# audio_breakout.net
KiCad netlist of a schematic drawn in EAGLE
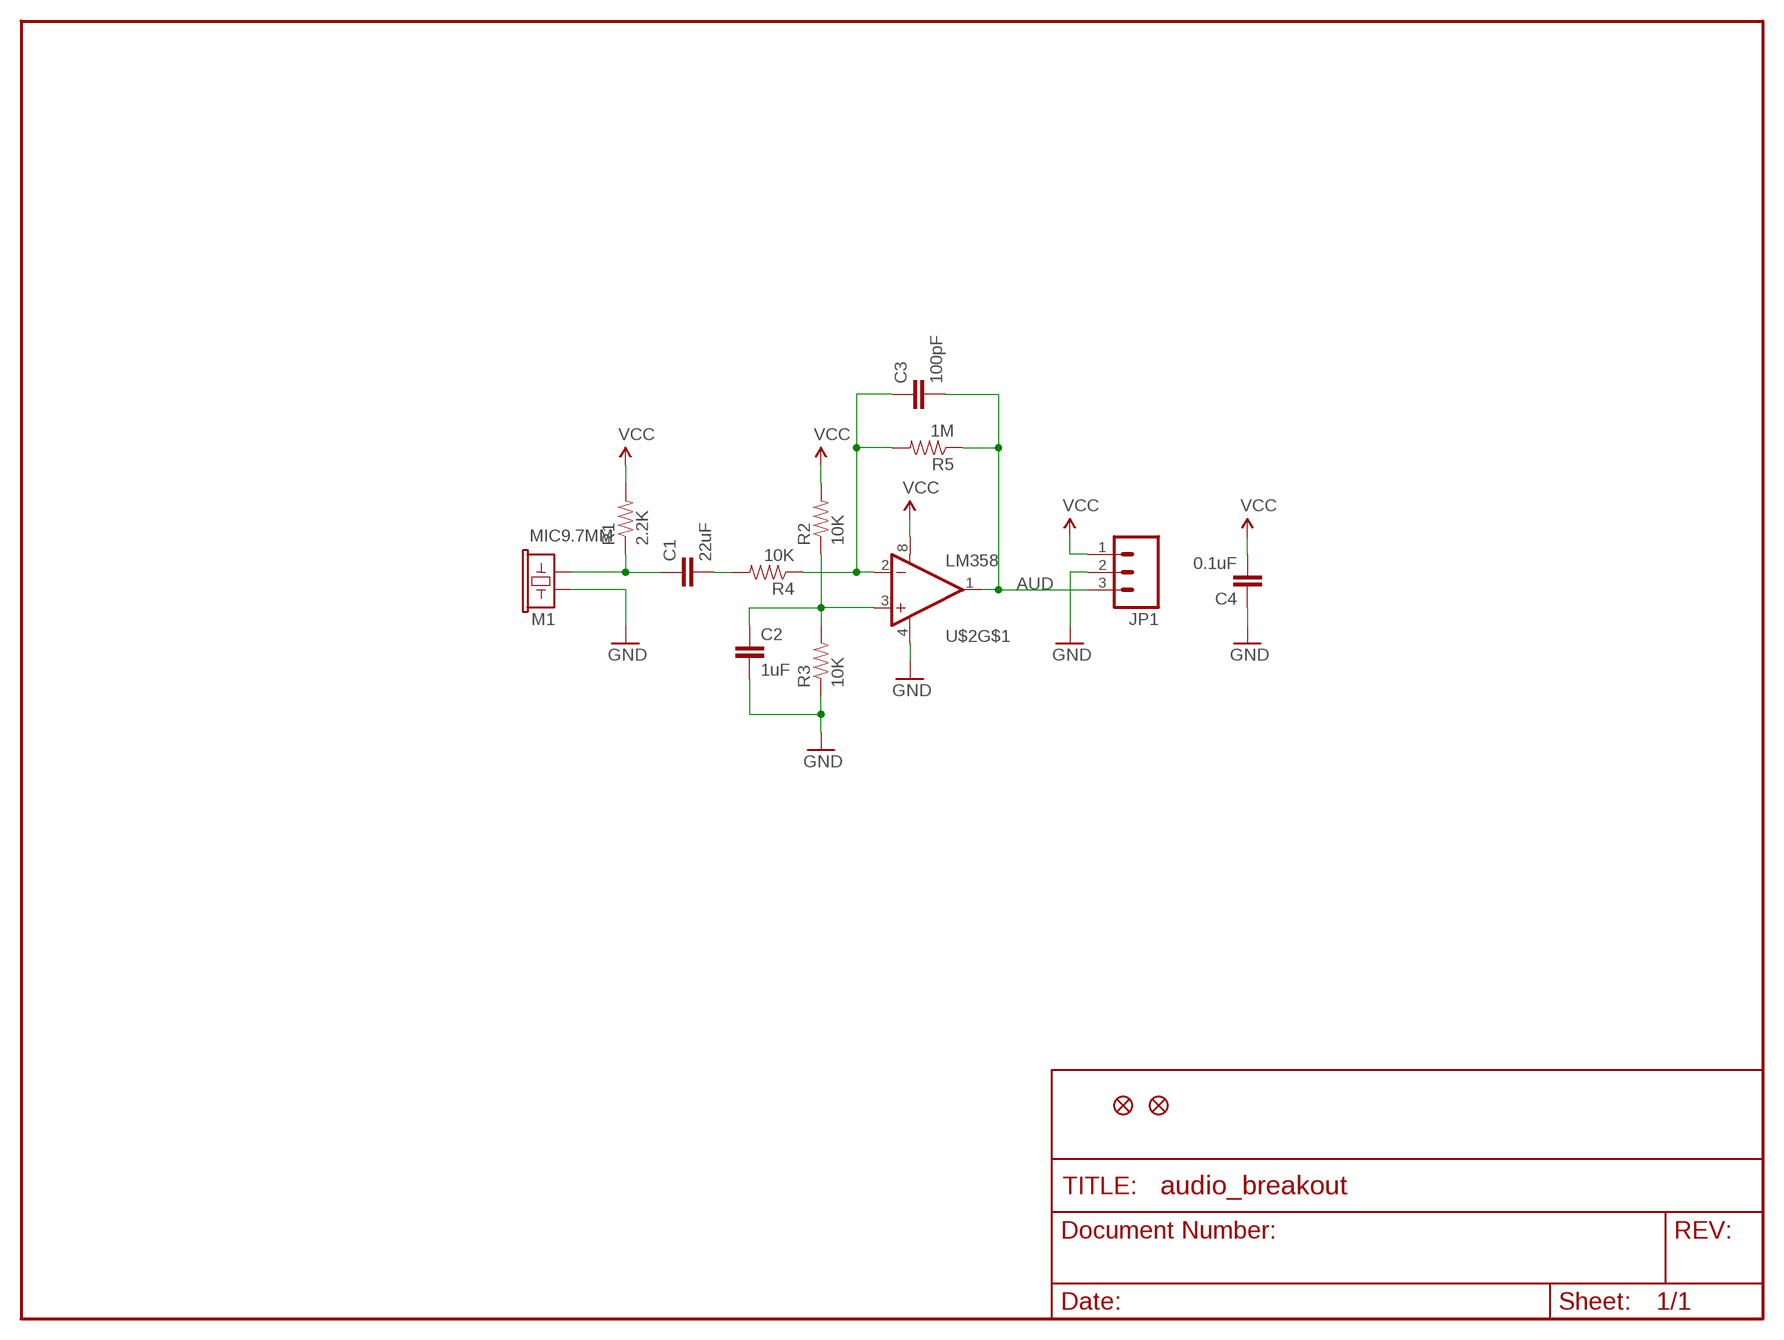
[diagram p0: schematic, sheet 1]

(export (version "E")
  (design (tool "Eeschema 10.0.6"))
  (components
    (comp (ref "C1")
      (value "22uF")
      (footprint "eagle-import:1206")
      (libsource (lib "eagle-import") (part "CAP1206"))
    )
    (comp (ref "C2")
      (value "1uF")
      (footprint "eagle-import:1206")
      (libsource (lib "eagle-import") (part "CAP1206"))
    )
    (comp (ref "C3")
      (value "100pF")
      (footprint "eagle-import:1206")
      (libsource (lib "eagle-import") (part "CAP1206"))
    )
    (comp (ref "C4")
      (value "0.1uF")
      (footprint "eagle-import:1206")
      (libsource (lib "eagle-import") (part "CAP1206"))
    )
    (comp (ref "JP1")
      (value "M03PTH")
      (footprint "eagle-import:1X03")
      (libsource (lib "eagle-import") (part "M03PTH"))
    )
    (comp (ref "JP2")
      (value "FIDUCIAL1X2")
      (footprint "eagle-import:FIDUCIAL-1X2")
      (libsource (lib "eagle-import") (part "FIDUCIAL1X2"))
    )
    (comp (ref "JP3")
      (value "FIDUCIAL1X2")
      (footprint "eagle-import:FIDUCIAL-1X2")
      (libsource (lib "eagle-import") (part "FIDUCIAL1X2"))
    )
    (comp (ref "M1")
      (value "MIC9.7MM")
      (footprint "eagle-import:MIC-9.7MM")
      (libsource (lib "eagle-import") (part "MIC9.7MM"))
    )
    (comp (ref "R1")
      (value "2.2K")
      (footprint "eagle-import:1206")
      (libsource (lib "eagle-import") (part "RESISTOR1206"))
    )
    (comp (ref "R2")
      (value "10K")
      (footprint "eagle-import:1206")
      (libsource (lib "eagle-import") (part "RESISTOR1206"))
    )
    (comp (ref "R3")
      (value "10K")
      (footprint "eagle-import:1206")
      (libsource (lib "eagle-import") (part "RESISTOR1206"))
    )
    (comp (ref "R4")
      (value "10K")
      (footprint "eagle-import:1206")
      (libsource (lib "eagle-import") (part "RESISTOR1206"))
    )
    (comp (ref "R5")
      (value "1M")
      (footprint "eagle-import:1206")
      (libsource (lib "eagle-import") (part "RESISTOR1206"))
    )
    (comp (ref "U$2")
      (value "LM358")
      (footprint "eagle-import:DIP08")
      (libsource (lib "eagle-import") (part "LM358"))
    )
  )
  (nets
    (net (code "1") (name "/AUD") (class "Default")
      (node (ref "C3") (pin "2") (pinfunction "2_2") (pintype "passive"))
      (node (ref "JP1") (pin "3") (pinfunction "3_3") (pintype "passive"))
      (node (ref "R5") (pin "1") (pinfunction "1_1") (pintype "passive"))
      (node (ref "U$2") (pin "1") (pinfunction "OUT_1") (pintype "output"))
    )
    (net (code "2") (name "GND") (class "Default")
      (node (ref "C2") (pin "2") (pinfunction "2_2") (pintype "passive"))
      (node (ref "C4") (pin "1") (pinfunction "1_1") (pintype "passive"))
      (node (ref "JP1") (pin "2") (pinfunction "2_2") (pintype "passive"))
      (node (ref "M1") (pin "2") (pinfunction "2_2") (pintype "passive"))
      (node (ref "R3") (pin "1") (pinfunction "1_1") (pintype "passive"))
      (node (ref "U$2") (pin "4") (pinfunction "V-_4") (pintype "power_in"))
    )
    (net (code "3") (name "Net-(C1-Pad1)") (class "Default")
      (node (ref "C1") (pin "1") (pinfunction "1_1") (pintype "passive"))
      (node (ref "M1") (pin "1") (pinfunction "1_1") (pintype "passive"))
      (node (ref "R1") (pin "1") (pinfunction "1_1") (pintype "passive"))
    )
    (net (code "4") (name "Net-(C1-Pad2)") (class "Default")
      (node (ref "C1") (pin "2") (pinfunction "2_2") (pintype "passive"))
      (node (ref "R4") (pin "2") (pinfunction "2_2") (pintype "passive"))
    )
    (net (code "5") (name "Net-(U$2A-+IN)") (class "Default")
      (node (ref "C2") (pin "1") (pinfunction "1_1") (pintype "passive"))
      (node (ref "R2") (pin "1") (pinfunction "1_1") (pintype "passive"))
      (node (ref "R3") (pin "2") (pinfunction "2_2") (pintype "passive"))
      (node (ref "U$2") (pin "3") (pinfunction "+IN_3") (pintype "input"))
    )
    (net (code "6") (name "Net-(U$2A--IN)") (class "Default")
      (node (ref "C3") (pin "1") (pinfunction "1_1") (pintype "passive"))
      (node (ref "R4") (pin "1") (pinfunction "1_1") (pintype "passive"))
      (node (ref "R5") (pin "2") (pinfunction "2_2") (pintype "passive"))
      (node (ref "U$2") (pin "2") (pinfunction "-IN_2") (pintype "input"))
    )
    (net (code "7") (name "VCC") (class "Default")
      (node (ref "C4") (pin "2") (pinfunction "2_2") (pintype "passive"))
      (node (ref "JP1") (pin "1") (pinfunction "1_1") (pintype "passive"))
      (node (ref "R1") (pin "2") (pinfunction "2_2") (pintype "passive"))
      (node (ref "R2") (pin "2") (pinfunction "2_2") (pintype "passive"))
      (node (ref "U$2") (pin "8") (pinfunction "V+_8") (pintype "power_in"))
    )
  )
)
